# Power.net
KiCad netlist of a schematic drawn in Altium Designer
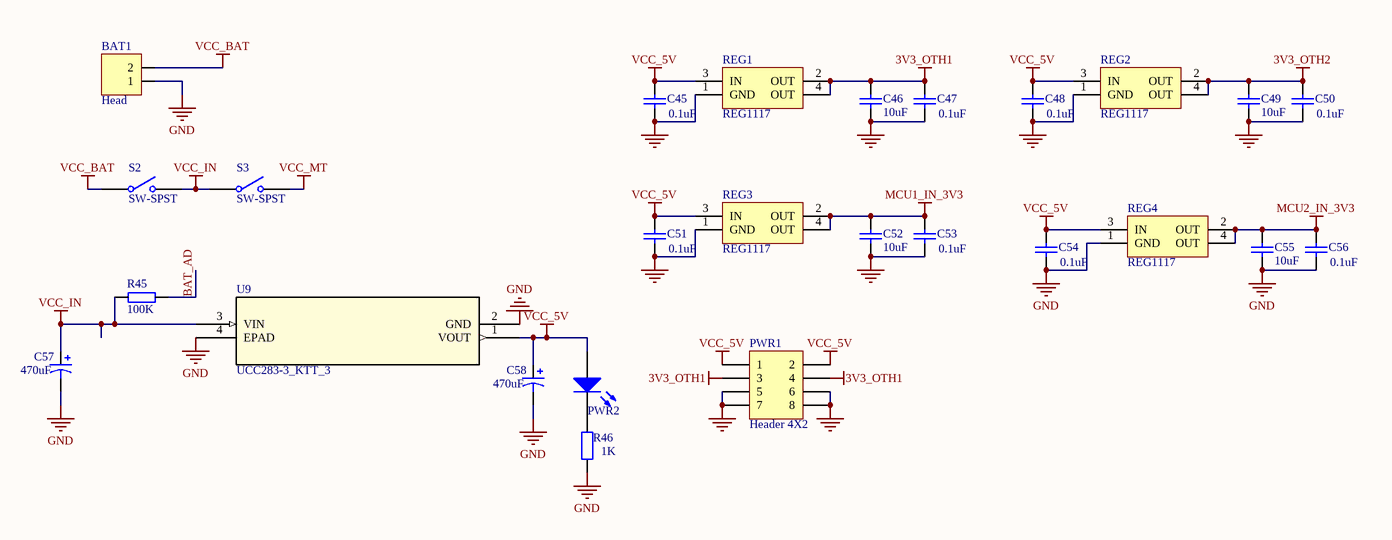
[diagram p0: Power.SchDoc]

(export (version "E")
  (design (tool "Eeschema 10.0.6"))
  (components
    (comp (ref "BAT1") (value "Head") (footprint "Head_Small") (libsource (lib "MyLib") (part "Head_My")))
    (comp (ref "C45")
      (value "0.1uF")
      (footprint "0805")
      (description "Capacitor (Semiconductor SIM Model)")
      (fields (field (name "Comment") "Cap Semi") (field (name "PUBLISHER") "Altium Limited"))
      (libsource (lib "KL26_main board") (part "Cap Semi"))
    )
    (comp (ref "C46")
      (value "10uF")
      (footprint "0805")
      (fields (field (name "Comment") "0.1uf"))
      (libsource (lib "KL26") (part "CAP1"))
    )
    (comp (ref "C47")
      (value "0.1uF")
      (footprint "0805")
      (description "Capacitor (Semiconductor SIM Model)")
      (fields (field (name "Comment") "Cap Semi") (field (name "PUBLISHER") "Altium Limited"))
      (libsource (lib "KL26_main board") (part "Cap Semi"))
    )
    (comp (ref "C48")
      (value "0.1uF")
      (footprint "0805")
      (description "Capacitor (Semiconductor SIM Model)")
      (fields (field (name "Comment") "Cap Semi") (field (name "PUBLISHER") "Altium Limited"))
      (libsource (lib "KL26_main board") (part "Cap Semi"))
    )
    (comp (ref "C49")
      (value "10uF")
      (footprint "0805")
      (fields (field (name "Comment") "0.1uf"))
      (libsource (lib "KL26") (part "CAP1"))
    )
    (comp (ref "C50")
      (value "0.1uF")
      (footprint "0805")
      (description "Capacitor (Semiconductor SIM Model)")
      (fields (field (name "Comment") "Cap Semi") (field (name "PUBLISHER") "Altium Limited"))
      (libsource (lib "KL26_main board") (part "Cap Semi"))
    )
    (comp (ref "C51")
      (value "0.1uF")
      (footprint "0805")
      (description "Capacitor (Semiconductor SIM Model)")
      (fields (field (name "Comment") "Cap Semi") (field (name "PUBLISHER") "Altium Limited"))
      (libsource (lib "KL26_main board") (part "Cap Semi"))
    )
    (comp (ref "C52")
      (value "10uF")
      (footprint "0805")
      (fields (field (name "Comment") "0.1uf"))
      (libsource (lib "KL26") (part "CAP1"))
    )
    (comp (ref "C53")
      (value "0.1uF")
      (footprint "0805")
      (description "Capacitor (Semiconductor SIM Model)")
      (fields (field (name "Comment") "Cap Semi") (field (name "PUBLISHER") "Altium Limited"))
      (libsource (lib "KL26_main board") (part "Cap Semi"))
    )
    (comp (ref "C54")
      (value "0.1uF")
      (footprint "0805")
      (description "Capacitor (Semiconductor SIM Model)")
      (fields (field (name "Comment") "Cap Semi") (field (name "PUBLISHER") "Altium Limited"))
      (libsource (lib "KL26_main board") (part "Cap Semi"))
    )
    (comp (ref "C55")
      (value "10uF")
      (footprint "0805")
      (fields (field (name "Comment") "0.1uf"))
      (libsource (lib "KL26") (part "CAP1"))
    )
    (comp (ref "C56")
      (value "0.1uF")
      (footprint "0805")
      (description "Capacitor (Semiconductor SIM Model)")
      (fields (field (name "Comment") "Cap Semi") (field (name "PUBLISHER") "Altium Limited"))
      (libsource (lib "KL26_main board") (part "Cap Semi"))
    )
    (comp (ref "C57")
      (value "470uF")
      (footprint "SMD-EC-F8")
      (description "Polarized Capacitor (Radial)")
      (fields (field (name "PUBLISHER") "Altium Limited"))
      (libsource (lib "Competion") (part "Cap Pol1"))
    )
    (comp (ref "C58")
      (value "470uF")
      (footprint "SMD-EC-F8")
      (description "Polarized Capacitor (Radial)")
      (fields (field (name "PUBLISHER") "Altium Limited"))
      (libsource (lib "Competion") (part "Cap Pol1"))
    )
    (comp (ref "PWR1")
      (value "Header 4X2")
      (footprint "HDR2X4")
      (description "Header, 4-Pin, Dual row")
      (fields (field (name "PUBLISHER") "Altium Limited"))
      (libsource (lib "Miscellaneous Connectors") (part "Header 4X2"))
    )
    (comp (ref "PWR2") (value "LED") (footprint "0805") (libsource (lib "xunpianzhen") (part "LED")))
    (comp (ref "R45") (value "100K") (footprint "0805") (libsource (lib "MyLib") (part "R")))
    (comp (ref "R46")
      (value "1K")
      (footprint "0805")
      (description "Resistor")
      (fields (field (name "Comment") "Res2") (field (name "PUBLISHER") "Altium Limited"))
      (libsource (lib "Miscellaneous Devices") (part "Res2"))
    )
    (comp (ref "REG1") (value "REG1117") (footprint "SOT-223") (libsource (lib "MyLib") (part "REG1117")))
    (comp (ref "REG2") (value "REG1117") (footprint "SOT-223") (libsource (lib "MyLib") (part "REG1117")))
    (comp (ref "REG3") (value "REG1117") (footprint "SOT-223") (libsource (lib "MyLib") (part "REG1117")))
    (comp (ref "REG4") (value "REG1117") (footprint "SOT-223") (libsource (lib "MyLib") (part "REG1117")))
    (comp (ref "S2")
      (value "SW-SPST")
      (footprint "Switch_N")
      (description "Single-Pole, Single-Throw Switch")
      (fields (field (name "PUBLISHER") "Altium Limited"))
      (libsource (lib "Miscellaneous Devices") (part "SW-SPST"))
    )
    (comp (ref "S3")
      (value "SW-SPST")
      (footprint "Switch_N")
      (description "Single-Pole, Single-Throw Switch")
      (fields (field (name "PUBLISHER") "Altium Limited"))
      (libsource (lib "Miscellaneous Devices") (part "SW-SPST"))
    )
    (comp (ref "U9")
      (value "UCC283-3_KTT_3")
      (footprint "KTT3_6P22X6P6")
      (description "Imported")
      (fields
        (field (name "MANUFACTURER_PART_NUMBER") "ucc283-3_ktt_3")
        (field (name "GENERIC_PART_NUMBER") "UCC283-3")
      )
      (libsource (lib "MyLib") (part "UCC283-3_KTT_3"))
    )
  )
  (nets
    (net (code "1") (name "/BAT_AD") (class "Default") (node (ref "R45") (pin "2") (pintype "passive")))
    (net (code "2") (name "3V3_OTH1") (class "Default")
      (node (ref "C46") (pin "2") (pinfunction "2_2") (pintype "passive"))
      (node (ref "C47") (pin "2") (pinfunction "2_2") (pintype "passive"))
      (node (ref "PWR1") (pin "3") (pinfunction "3_3") (pintype "passive"))
      (node (ref "PWR1") (pin "4") (pinfunction "4_4") (pintype "passive"))
      (node (ref "REG1") (pin "2") (pinfunction "OUT_2") (pintype "power_in"))
      (node (ref "REG1") (pin "4") (pinfunction "OUT_4") (pintype "power_in"))
    )
    (net (code "3") (name "3V3_OTH2") (class "Default")
      (node (ref "C49") (pin "2") (pinfunction "2_2") (pintype "passive"))
      (node (ref "C50") (pin "2") (pinfunction "2_2") (pintype "passive"))
      (node (ref "REG2") (pin "2") (pinfunction "OUT_2") (pintype "power_in"))
      (node (ref "REG2") (pin "4") (pinfunction "OUT_4") (pintype "power_in"))
    )
    (net (code "4") (name "GND") (class "Default")
      (node (ref "BAT1") (pin "1") (pinfunction "1_1") (pintype "passive"))
      (node (ref "C45") (pin "1") (pinfunction "1_1") (pintype "passive"))
      (node (ref "C46") (pin "1") (pinfunction "1_1") (pintype "passive"))
      (node (ref "C47") (pin "1") (pinfunction "1_1") (pintype "passive"))
      (node (ref "C48") (pin "1") (pinfunction "1_1") (pintype "passive"))
      (node (ref "C49") (pin "1") (pinfunction "1_1") (pintype "passive"))
      (node (ref "C50") (pin "1") (pinfunction "1_1") (pintype "passive"))
      (node (ref "C51") (pin "1") (pinfunction "1_1") (pintype "passive"))
      (node (ref "C52") (pin "1") (pinfunction "1_1") (pintype "passive"))
      (node (ref "C53") (pin "1") (pinfunction "1_1") (pintype "passive"))
      (node (ref "C54") (pin "1") (pinfunction "1_1") (pintype "passive"))
      (node (ref "C55") (pin "1") (pinfunction "1_1") (pintype "passive"))
      (node (ref "C56") (pin "1") (pinfunction "1_1") (pintype "passive"))
      (node (ref "C57") (pin "2") (pinfunction "2_2") (pintype "passive"))
      (node (ref "C58") (pin "2") (pinfunction "2_2") (pintype "passive"))
      (node (ref "PWR1") (pin "5") (pinfunction "5_5") (pintype "passive"))
      (node (ref "PWR1") (pin "6") (pinfunction "6_6") (pintype "passive"))
      (node (ref "PWR1") (pin "7") (pinfunction "7_7") (pintype "passive"))
      (node (ref "PWR1") (pin "8") (pinfunction "8_8") (pintype "passive"))
      (node (ref "R46") (pin "1") (pinfunction "1_1") (pintype "passive"))
      (node (ref "REG1") (pin "1") (pinfunction "GND_1") (pintype "passive"))
      (node (ref "REG2") (pin "1") (pinfunction "GND_1") (pintype "passive"))
      (node (ref "REG3") (pin "1") (pinfunction "GND_1") (pintype "passive"))
      (node (ref "REG4") (pin "1") (pinfunction "GND_1") (pintype "passive"))
      (node (ref "U9") (pin "2") (pinfunction "GND_2") (pintype "power_in"))
      (node (ref "U9") (pin "4") (pinfunction "EPAD_4") (pintype "passive"))
    )
    (net (code "5") (name "MCU1_IN_3V3") (class "Default")
      (node (ref "C52") (pin "2") (pinfunction "2_2") (pintype "passive"))
      (node (ref "C53") (pin "2") (pinfunction "2_2") (pintype "passive"))
      (node (ref "REG3") (pin "2") (pinfunction "OUT_2") (pintype "power_in"))
      (node (ref "REG3") (pin "4") (pinfunction "OUT_4") (pintype "power_in"))
    )
    (net (code "6") (name "MCU2_IN_3V3") (class "Default")
      (node (ref "C55") (pin "2") (pinfunction "2_2") (pintype "passive"))
      (node (ref "C56") (pin "2") (pinfunction "2_2") (pintype "passive"))
      (node (ref "REG4") (pin "2") (pinfunction "OUT_2") (pintype "power_in"))
      (node (ref "REG4") (pin "4") (pinfunction "OUT_4") (pintype "power_in"))
    )
    (net (code "7") (name "Net-(PWR2-K)") (class "Default")
      (node (ref "PWR2") (pin "2") (pinfunction "K_2") (pintype "passive"))
      (node (ref "R46") (pin "2") (pinfunction "2_2") (pintype "passive"))
    )
    (net (code "8") (name "VCC_5V") (class "Default")
      (node (ref "C45") (pin "2") (pinfunction "2_2") (pintype "passive"))
      (node (ref "C48") (pin "2") (pinfunction "2_2") (pintype "passive"))
      (node (ref "C51") (pin "2") (pinfunction "2_2") (pintype "passive"))
      (node (ref "C54") (pin "2") (pinfunction "2_2") (pintype "passive"))
      (node (ref "C58") (pin "1") (pinfunction "1_1") (pintype "passive"))
      (node (ref "PWR1") (pin "1") (pinfunction "1_1") (pintype "passive"))
      (node (ref "PWR1") (pin "2") (pinfunction "2_2") (pintype "passive"))
      (node (ref "PWR2") (pin "1") (pinfunction "A_1") (pintype "passive"))
      (node (ref "REG1") (pin "3") (pinfunction "IN_3") (pintype "passive"))
      (node (ref "REG2") (pin "3") (pinfunction "IN_3") (pintype "passive"))
      (node (ref "REG3") (pin "3") (pinfunction "IN_3") (pintype "passive"))
      (node (ref "REG4") (pin "3") (pinfunction "IN_3") (pintype "passive"))
      (node (ref "U9") (pin "1") (pinfunction "VOUT_1") (pintype "output"))
    )
    (net (code "9") (name "VCC_BAT") (class "Default")
      (node (ref "BAT1") (pin "2") (pinfunction "2_2") (pintype "passive"))
      (node (ref "S2") (pin "1") (pinfunction "COMMON_1") (pintype "passive"))
    )
    (net (code "10") (name "VCC_IN") (class "Default")
      (node (ref "C57") (pin "1") (pinfunction "1_1") (pintype "passive"))
      (node (ref "R45") (pin "1") (pintype "passive"))
      (node (ref "S2") (pin "2") (pinfunction "NO_2") (pintype "passive"))
      (node (ref "S3") (pin "1") (pinfunction "COMMON_1") (pintype "passive"))
      (node (ref "U9") (pin "3") (pinfunction "VIN_3") (pintype "input"))
    )
    (net (code "11") (name "VCC_MT") (class "Default")
      (node (ref "S3") (pin "2") (pinfunction "NO_2") (pintype "passive"))
    )
  )
)
